# SDRAM.net
KiCad netlist of a schematic drawn in Altium Designer
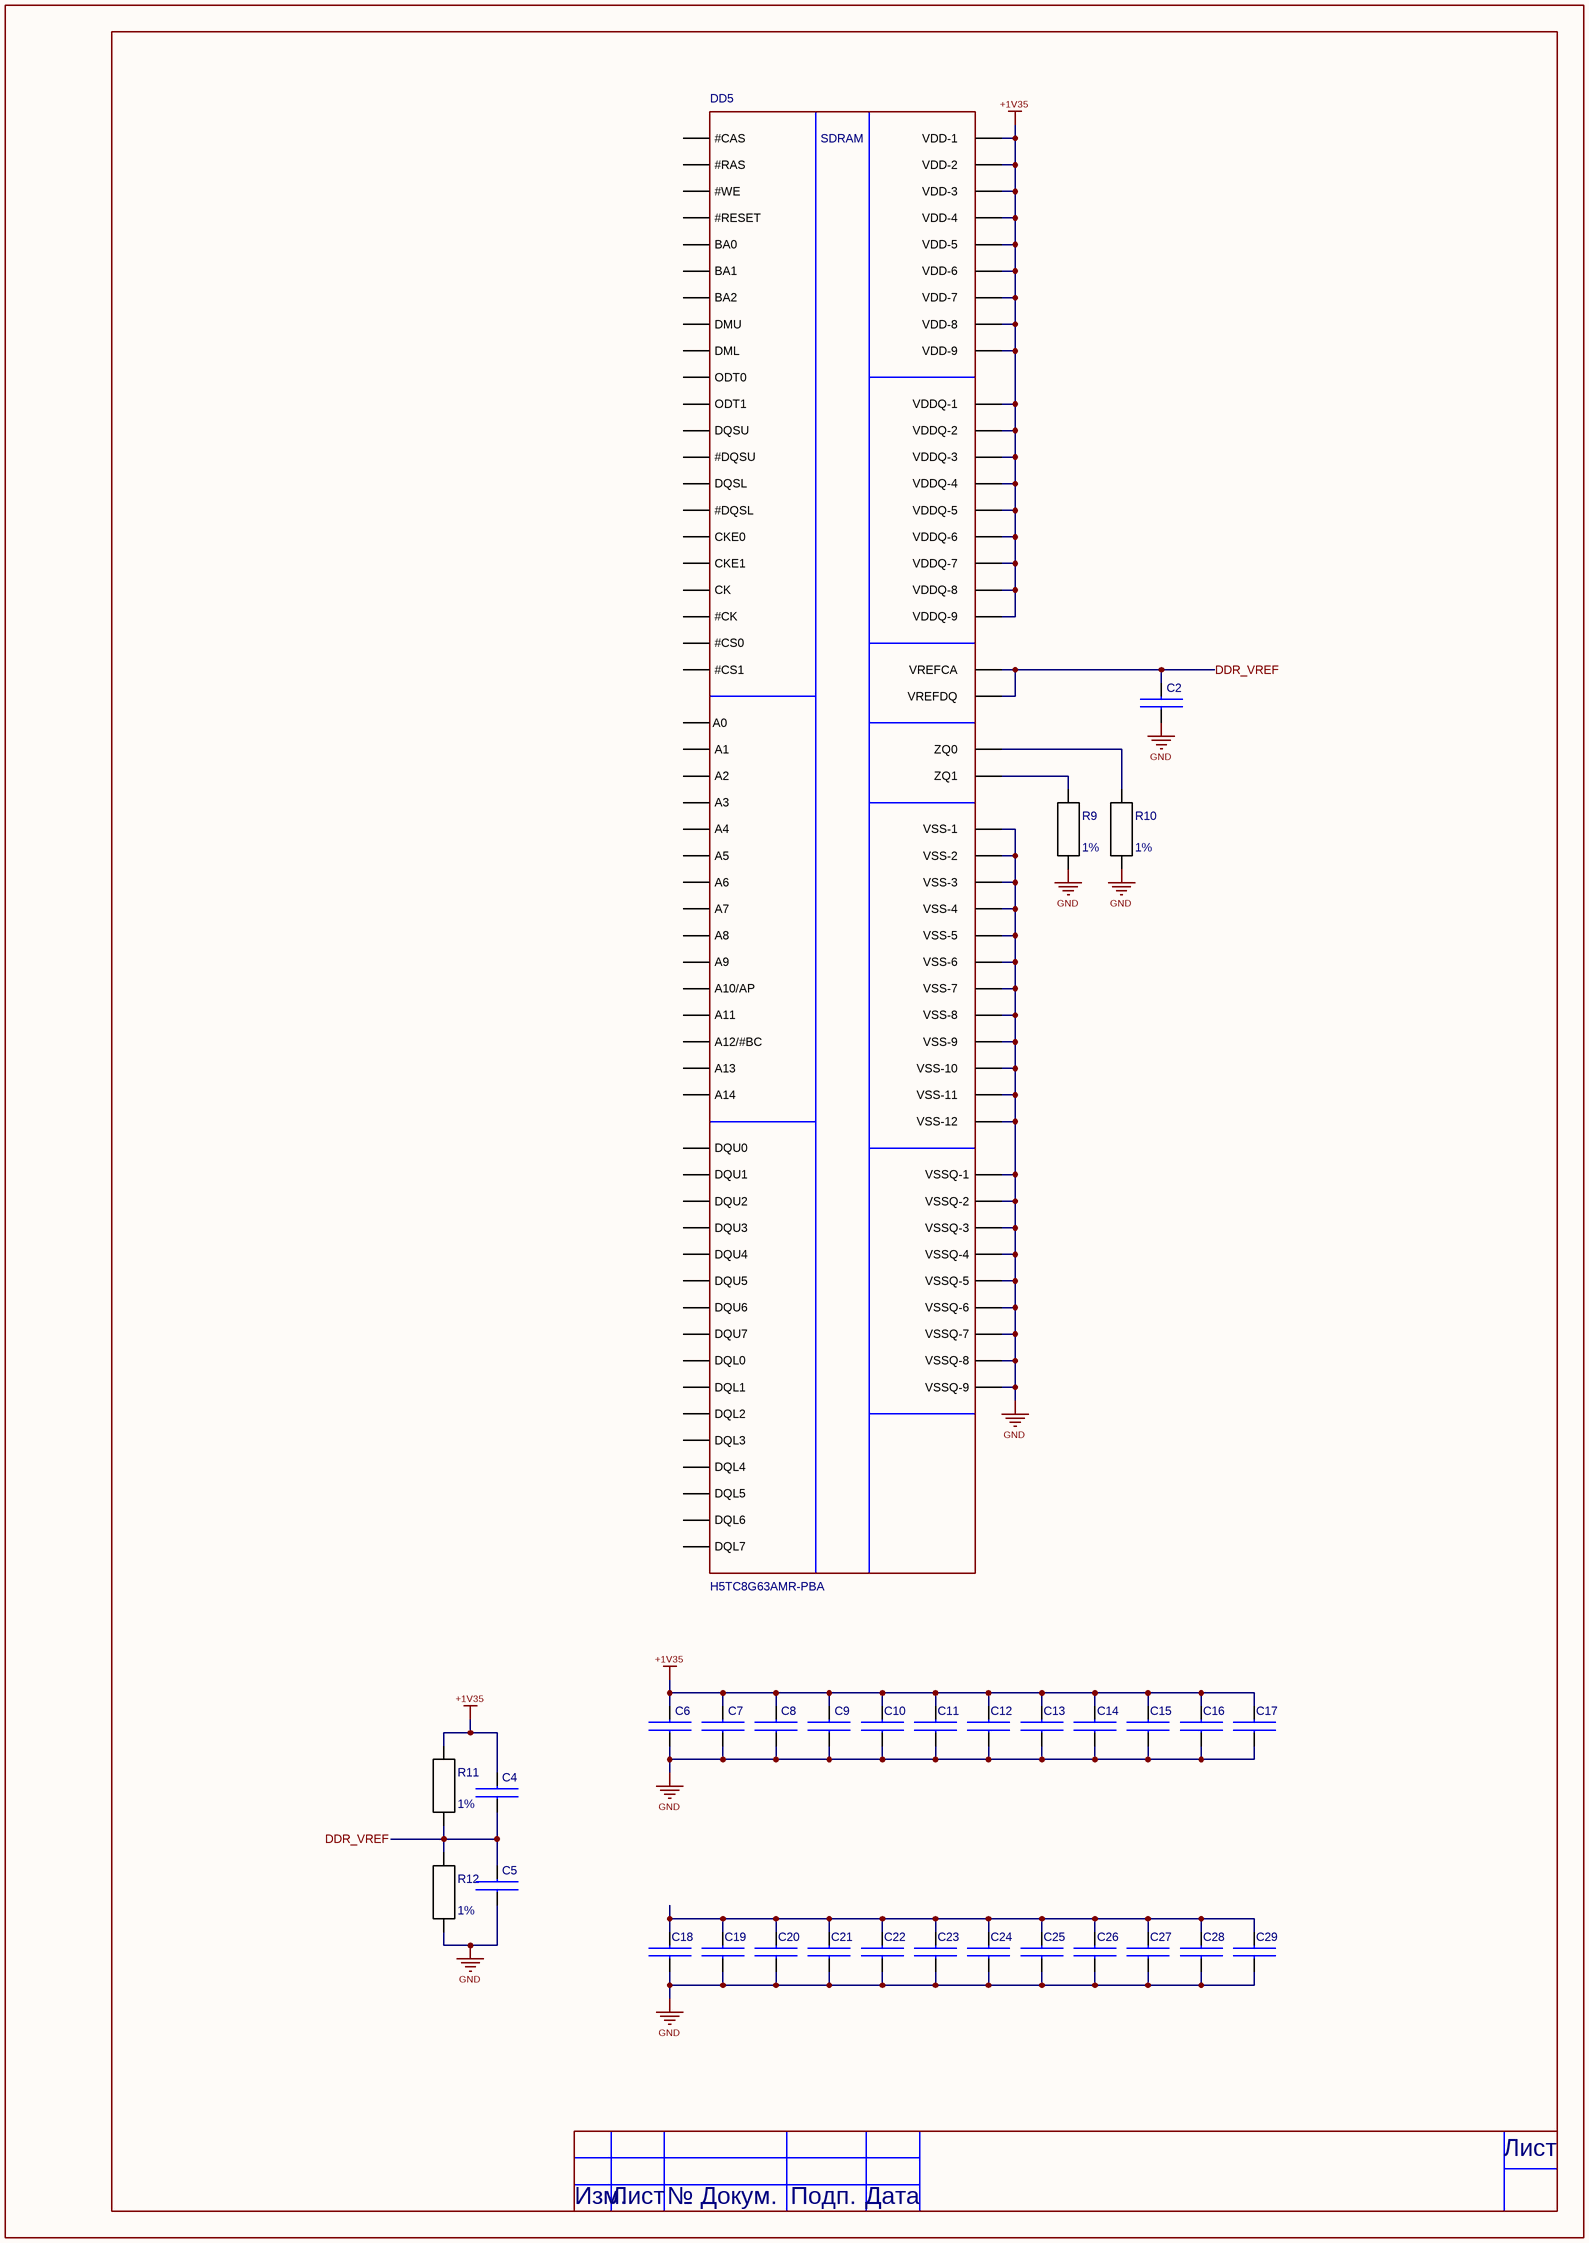
[diagram p0: SDRAM.SchDoc]

(export (version "E")
  (design (tool "Eeschema 10.0.6"))
  (components
    (comp (ref "C2")
      (value "0402-0.1uF-50V-10%-X7R")
      (fields (field (name "TOLERANCE") "10%"))
      (libsource (lib "altium-import") (part "root_1_mirrored__*"))
    )
    (comp (ref "C4")
      (value "0402-0.1uF-50V-10%-X7R")
      (fields (field (name "TOLERANCE") "10%"))
      (libsource (lib "altium-import") (part "root_1__*"))
    )
    (comp (ref "C5")
      (value "0402-0.1uF-50V-10%-X7R")
      (fields (field (name "TOLERANCE") "10%"))
      (libsource (lib "altium-import") (part "root_1__*"))
    )
    (comp (ref "C6")
      (value "0402-0.1uF-50V-10%-X7R")
      (fields (field (name "TOLERANCE") "10%"))
      (libsource (lib "altium-import") (part "root_1__*"))
    )
    (comp (ref "C7")
      (value "0402-0.1uF-50V-10%-X7R")
      (fields (field (name "TOLERANCE") "10%"))
      (libsource (lib "altium-import") (part "root_1__*"))
    )
    (comp (ref "C8")
      (value "0402-0.1uF-50V-10%-X7R")
      (fields (field (name "TOLERANCE") "10%"))
      (libsource (lib "altium-import") (part "root_1__*"))
    )
    (comp (ref "C9")
      (value "0402-0.1uF-50V-10%-X7R")
      (fields (field (name "TOLERANCE") "10%"))
      (libsource (lib "altium-import") (part "root_1__*"))
    )
    (comp (ref "C10")
      (value "0402-0.1uF-50V-10%-X7R")
      (fields (field (name "TOLERANCE") "10%"))
      (libsource (lib "altium-import") (part "root_1__*"))
    )
    (comp (ref "C11")
      (value "0402-0.1uF-50V-10%-X7R")
      (fields (field (name "TOLERANCE") "10%"))
      (libsource (lib "altium-import") (part "root_1__*"))
    )
    (comp (ref "C12")
      (value "0402-0.1uF-50V-10%-X7R")
      (fields (field (name "TOLERANCE") "10%"))
      (libsource (lib "altium-import") (part "root_1__*"))
    )
    (comp (ref "C13")
      (value "0402-0.1uF-50V-10%-X7R")
      (fields (field (name "TOLERANCE") "10%"))
      (libsource (lib "altium-import") (part "root_1__*"))
    )
    (comp (ref "C14")
      (value "0402-0.1uF-50V-10%-X7R")
      (fields (field (name "TOLERANCE") "10%"))
      (libsource (lib "altium-import") (part "root_1__*"))
    )
    (comp (ref "C15")
      (value "0402-0.1uF-50V-10%-X7R")
      (fields (field (name "TOLERANCE") "10%"))
      (libsource (lib "altium-import") (part "root_1__*"))
    )
    (comp (ref "C16")
      (value "0402-0.1uF-50V-10%-X7R")
      (fields (field (name "TOLERANCE") "10%"))
      (libsource (lib "altium-import") (part "root_1__*"))
    )
    (comp (ref "C17")
      (value "0402-0.1uF-50V-10%-X7R")
      (fields (field (name "TOLERANCE") "10%"))
      (libsource (lib "altium-import") (part "root_1__*"))
    )
    (comp (ref "C18")
      (value "0402-0.1uF-50V-10%-X7R")
      (fields (field (name "TOLERANCE") "10%"))
      (libsource (lib "altium-import") (part "root_1__*"))
    )
    (comp (ref "C19")
      (value "0402-0.1uF-50V-10%-X7R")
      (fields (field (name "TOLERANCE") "10%"))
      (libsource (lib "altium-import") (part "root_1__*"))
    )
    (comp (ref "C20")
      (value "0402-0.1uF-50V-10%-X7R")
      (fields (field (name "TOLERANCE") "10%"))
      (libsource (lib "altium-import") (part "root_1__*"))
    )
    (comp (ref "C21")
      (value "0402-0.1uF-50V-10%-X7R")
      (fields (field (name "TOLERANCE") "10%"))
      (libsource (lib "altium-import") (part "root_1__*"))
    )
    (comp (ref "C22")
      (value "0402-0.1uF-50V-10%-X7R")
      (fields (field (name "TOLERANCE") "10%"))
      (libsource (lib "altium-import") (part "root_1__*"))
    )
    (comp (ref "C23")
      (value "0402-0.1uF-50V-10%-X7R")
      (fields (field (name "TOLERANCE") "10%"))
      (libsource (lib "altium-import") (part "root_1__*"))
    )
    (comp (ref "C24")
      (value "0402-0.1uF-50V-10%-X7R")
      (fields (field (name "TOLERANCE") "10%"))
      (libsource (lib "altium-import") (part "root_1__*"))
    )
    (comp (ref "C25")
      (value "0402-0.1uF-50V-10%-X7R")
      (fields (field (name "TOLERANCE") "10%"))
      (libsource (lib "altium-import") (part "root_1__*"))
    )
    (comp (ref "C26")
      (value "0402-0.1uF-50V-10%-X7R")
      (fields (field (name "TOLERANCE") "10%"))
      (libsource (lib "altium-import") (part "root_1__*"))
    )
    (comp (ref "C27")
      (value "0402-0.1uF-50V-10%-X7R")
      (fields (field (name "TOLERANCE") "10%"))
      (libsource (lib "altium-import") (part "root_1__*"))
    )
    (comp (ref "C28")
      (value "0402-0.1uF-50V-10%-X7R")
      (fields (field (name "TOLERANCE") "10%"))
      (libsource (lib "altium-import") (part "root_1__*"))
    )
    (comp (ref "C29")
      (value "0402-0.1uF-50V-10%-X7R")
      (fields (field (name "TOLERANCE") "10%"))
      (libsource (lib "altium-import") (part "root_1__*"))
    )
    (comp (ref "DD5") (value "H5TC8G63AMR-PBA") (libsource (lib "altium-import") (part "root_0__*")))
    (comp (ref "R9")
      (value "0402-243R-1%-1/16 W-100ppm")
      (fields (field (name "TOLERANCE") "1%"))
      (libsource (lib "altium-import") (part "root_3_mirrored__*"))
    )
    (comp (ref "R10")
      (value "0402-243R-1%-1/16 W-100ppm")
      (fields (field (name "TOLERANCE") "1%"))
      (libsource (lib "altium-import") (part "root_3__*"))
    )
    (comp (ref "R11")
      (value "0402-2k-1%-1/16 W-100ppm")
      (fields (field (name "TOLERANCE") "1%"))
      (libsource (lib "") (part "root_1__*_1"))
    )
    (comp (ref "R12")
      (value "0402-2k-1%-1/16 W-100ppm")
      (fields (field (name "TOLERANCE") "1%"))
      (libsource (lib "") (part "root_1__*_1"))
    )
  )
  (nets
    (net (code "1") (name "+1V35") (class "Default")
      (node (ref "C10") (pin "2") (pinfunction "2_2") (pintype "passive"))
      (node (ref "C11") (pin "2") (pinfunction "2_2") (pintype "passive"))
      (node (ref "C12") (pin "2") (pinfunction "2_2") (pintype "passive"))
      (node (ref "C13") (pin "2") (pinfunction "2_2") (pintype "passive"))
      (node (ref "C14") (pin "2") (pinfunction "2_2") (pintype "passive"))
      (node (ref "C15") (pin "2") (pinfunction "2_2") (pintype "passive"))
      (node (ref "C16") (pin "2") (pinfunction "2_2") (pintype "passive"))
      (node (ref "C17") (pin "2") (pinfunction "2_2") (pintype "passive"))
      (node (ref "C4") (pin "2") (pinfunction "2_2") (pintype "passive"))
      (node (ref "C6") (pin "2") (pinfunction "2_2") (pintype "passive"))
      (node (ref "C7") (pin "2") (pinfunction "2_2") (pintype "passive"))
      (node (ref "C8") (pin "2") (pinfunction "2_2") (pintype "passive"))
      (node (ref "C9") (pin "2") (pinfunction "2_2") (pintype "passive"))
      (node (ref "DD5") (pin "A1") (pinfunction "VDDQ-1_A1") (pintype "passive"))
      (node (ref "DD5") (pin "A8") (pinfunction "VDDQ-6_A8") (pintype "passive"))
      (node (ref "DD5") (pin "B2") (pinfunction "VDD-3_B2") (pintype "passive"))
      (node (ref "DD5") (pin "C1") (pinfunction "VDDQ-2_C1") (pintype "passive"))
      (node (ref "DD5") (pin "C9") (pinfunction "VDDQ-7_C9") (pintype "passive"))
      (node (ref "DD5") (pin "D2") (pinfunction "VDDQ-4_D2") (pintype "passive"))
      (node (ref "DD5") (pin "D9") (pinfunction "VDD-7_D9") (pintype "passive"))
      (node (ref "DD5") (pin "E9") (pinfunction "VDDQ-8_E9") (pintype "passive"))
      (node (ref "DD5") (pin "F1") (pinfunction "VDDQ-3_F1") (pintype "passive"))
      (node (ref "DD5") (pin "G7") (pinfunction "VDD-5_G7") (pintype "passive"))
      (node (ref "DD5") (pin "H2") (pinfunction "VDDQ-5_H2") (pintype "passive"))
      (node (ref "DD5") (pin "H9") (pinfunction "VDDQ-9_H9") (pintype "passive"))
      (node (ref "DD5") (pin "K2") (pinfunction "VDD-4_K2") (pintype "passive"))
      (node (ref "DD5") (pin "K8") (pinfunction "VDD-6_K8") (pintype "passive"))
      (node (ref "DD5") (pin "N1") (pinfunction "VDD-1_N1") (pintype "passive"))
      (node (ref "DD5") (pin "N9") (pinfunction "VDD-8_N9") (pintype "passive"))
      (node (ref "DD5") (pin "R1") (pinfunction "VDD-2_R1") (pintype "passive"))
      (node (ref "DD5") (pin "R9") (pinfunction "VDD-9_R9") (pintype "passive"))
      (node (ref "R11") (pin "2") (pinfunction "2_2") (pintype "passive"))
    )
    (net (code "2") (name "/DDR_VREF") (class "Default")
      (node (ref "C2") (pin "2") (pinfunction "2_2") (pintype "passive"))
      (node (ref "C4") (pin "1") (pinfunction "1_1") (pintype "passive"))
      (node (ref "C5") (pin "2") (pinfunction "2_2") (pintype "passive"))
      (node (ref "DD5") (pin "H1") (pinfunction "VREFDQ_H1") (pintype "passive"))
      (node (ref "DD5") (pin "M8") (pinfunction "VREFCA_M8") (pintype "passive"))
      (node (ref "R11") (pin "1") (pinfunction "1_1") (pintype "passive"))
      (node (ref "R12") (pin "2") (pinfunction "2_2") (pintype "passive"))
    )
    (net (code "3") (name "GND") (class "Default")
      (node (ref "C10") (pin "1") (pinfunction "1_1") (pintype "passive"))
      (node (ref "C11") (pin "1") (pinfunction "1_1") (pintype "passive"))
      (node (ref "C12") (pin "1") (pinfunction "1_1") (pintype "passive"))
      (node (ref "C13") (pin "1") (pinfunction "1_1") (pintype "passive"))
      (node (ref "C14") (pin "1") (pinfunction "1_1") (pintype "passive"))
      (node (ref "C15") (pin "1") (pinfunction "1_1") (pintype "passive"))
      (node (ref "C16") (pin "1") (pinfunction "1_1") (pintype "passive"))
      (node (ref "C17") (pin "1") (pinfunction "1_1") (pintype "passive"))
      (node (ref "C18") (pin "1") (pinfunction "1_1") (pintype "passive"))
      (node (ref "C19") (pin "1") (pinfunction "1_1") (pintype "passive"))
      (node (ref "C2") (pin "1") (pinfunction "1_1") (pintype "passive"))
      (node (ref "C20") (pin "1") (pinfunction "1_1") (pintype "passive"))
      (node (ref "C21") (pin "1") (pinfunction "1_1") (pintype "passive"))
      (node (ref "C22") (pin "1") (pinfunction "1_1") (pintype "passive"))
      (node (ref "C23") (pin "1") (pinfunction "1_1") (pintype "passive"))
      (node (ref "C24") (pin "1") (pinfunction "1_1") (pintype "passive"))
      (node (ref "C25") (pin "1") (pinfunction "1_1") (pintype "passive"))
      (node (ref "C26") (pin "1") (pinfunction "1_1") (pintype "passive"))
      (node (ref "C27") (pin "1") (pinfunction "1_1") (pintype "passive"))
      (node (ref "C28") (pin "1") (pinfunction "1_1") (pintype "passive"))
      (node (ref "C29") (pin "1") (pinfunction "1_1") (pintype "passive"))
      (node (ref "C5") (pin "1") (pinfunction "1_1") (pintype "passive"))
      (node (ref "C6") (pin "1") (pinfunction "1_1") (pintype "passive"))
      (node (ref "C7") (pin "1") (pinfunction "1_1") (pintype "passive"))
      (node (ref "C8") (pin "1") (pinfunction "1_1") (pintype "passive"))
      (node (ref "C9") (pin "1") (pinfunction "1_1") (pintype "passive"))
      (node (ref "DD5") (pin "A9") (pinfunction "VSS-9_A9") (pintype "power_in"))
      (node (ref "DD5") (pin "B1") (pinfunction "VSSQ-1_B1") (pintype "power_in"))
      (node (ref "DD5") (pin "B3") (pinfunction "VSS-6_B3") (pintype "power_in"))
      (node (ref "DD5") (pin "B9") (pinfunction "VSSQ-7_B9") (pintype "power_in"))
      (node (ref "DD5") (pin "D1") (pinfunction "VSSQ-2_D1") (pintype "power_in"))
      (node (ref "DD5") (pin "D8") (pinfunction "VSSQ-5_D8") (pintype "power_in"))
      (node (ref "DD5") (pin "E1") (pinfunction "VSS-1_E1") (pintype "power_in"))
      (node (ref "DD5") (pin "E2") (pinfunction "VSSQ-4_E2") (pintype "power_in"))
      (node (ref "DD5") (pin "E8") (pinfunction "VSSQ-6_E8") (pintype "power_in"))
      (node (ref "DD5") (pin "F9") (pinfunction "VSSQ-8_F9") (pintype "power_in"))
      (node (ref "DD5") (pin "G1") (pinfunction "VSSQ-3_G1") (pintype "power_in"))
      (node (ref "DD5") (pin "G8") (pinfunction "VSS-7_G8") (pintype "power_in"))
      (node (ref "DD5") (pin "G9") (pinfunction "VSSQ-9_G9") (pintype "power_in"))
      (node (ref "DD5") (pin "J2") (pinfunction "VSS-5_J2") (pintype "power_in"))
      (node (ref "DD5") (pin "J8") (pinfunction "VSS-8_J8") (pintype "power_in"))
      (node (ref "DD5") (pin "M1") (pinfunction "VSS-2_M1") (pintype "power_in"))
      (node (ref "DD5") (pin "M9") (pinfunction "VSS-10_M9") (pintype "power_in"))
      (node (ref "DD5") (pin "P1") (pinfunction "VSS-3_P1") (pintype "power_in"))
      (node (ref "DD5") (pin "P9") (pinfunction "VSS-11_P9") (pintype "power_in"))
      (node (ref "DD5") (pin "T1") (pinfunction "VSS-4_T1") (pintype "power_in"))
      (node (ref "DD5") (pin "T9") (pinfunction "VSS-12_T9") (pintype "power_in"))
      (node (ref "R10") (pin "2") (pinfunction "2_2") (pintype "passive"))
      (node (ref "R12") (pin "1") (pinfunction "1_1") (pintype "passive"))
      (node (ref "R9") (pin "2") (pinfunction "2_2") (pintype "passive"))
    )
    (net (code "4") (name "Net-(C18-Pad2)") (class "Default")
      (node (ref "C18") (pin "2") (pinfunction "2_2") (pintype "passive"))
      (node (ref "C19") (pin "2") (pinfunction "2_2") (pintype "passive"))
      (node (ref "C20") (pin "2") (pinfunction "2_2") (pintype "passive"))
      (node (ref "C21") (pin "2") (pinfunction "2_2") (pintype "passive"))
      (node (ref "C22") (pin "2") (pinfunction "2_2") (pintype "passive"))
      (node (ref "C23") (pin "2") (pinfunction "2_2") (pintype "passive"))
      (node (ref "C24") (pin "2") (pinfunction "2_2") (pintype "passive"))
      (node (ref "C25") (pin "2") (pinfunction "2_2") (pintype "passive"))
      (node (ref "C26") (pin "2") (pinfunction "2_2") (pintype "passive"))
      (node (ref "C27") (pin "2") (pinfunction "2_2") (pintype "passive"))
      (node (ref "C28") (pin "2") (pinfunction "2_2") (pintype "passive"))
      (node (ref "C29") (pin "2") (pinfunction "2_2") (pintype "passive"))
    )
    (net (code "5") (name "Net-(DD5-ZQ0)") (class "Default")
      (node (ref "DD5") (pin "L8") (pinfunction "ZQ0_L8") (pintype "passive"))
      (node (ref "R10") (pin "1") (pinfunction "1_1") (pintype "passive"))
    )
    (net (code "6") (name "Net-(DD5-ZQ1)") (class "Default")
      (node (ref "DD5") (pin "L9") (pinfunction "ZQ1_L9") (pintype "passive"))
      (node (ref "R9") (pin "1") (pinfunction "1_1") (pintype "passive"))
    )
    (net (code "7") (name "unconnected-(DD5-#CAS-PadK3)") (class "Default")
      (node (ref "DD5") (pin "K3") (pinfunction "#CAS_K3") (pintype "passive"))
    )
    (net (code "8") (name "unconnected-(DD5-#CK-PadK7)") (class "Default")
      (node (ref "DD5") (pin "K7") (pinfunction "#CK_K7") (pintype "passive"))
    )
    (net (code "9") (name "unconnected-(DD5-#CS0-PadL2)") (class "Default")
      (node (ref "DD5") (pin "L2") (pinfunction "#CS0_L2") (pintype "passive"))
    )
    (net (code "10") (name "unconnected-(DD5-#CS1-PadL1)") (class "Default")
      (node (ref "DD5") (pin "L1") (pinfunction "#CS1_L1") (pintype "passive"))
    )
    (net (code "11") (name "unconnected-(DD5-#DQSL-PadG3)") (class "Default")
      (node (ref "DD5") (pin "G3") (pinfunction "#DQSL_G3") (pintype "passive"))
    )
    (net (code "12") (name "unconnected-(DD5-#DQSU-PadB7)") (class "Default")
      (node (ref "DD5") (pin "B7") (pinfunction "#DQSU_B7") (pintype "passive"))
    )
    (net (code "13") (name "unconnected-(DD5-#RAS-PadJ3)") (class "Default")
      (node (ref "DD5") (pin "J3") (pinfunction "#RAS_J3") (pintype "passive"))
    )
    (net (code "14") (name "unconnected-(DD5-#RESET-PadT2)") (class "Default")
      (node (ref "DD5") (pin "T2") (pinfunction "#RESET_T2") (pintype "passive"))
    )
    (net (code "15") (name "unconnected-(DD5-#WE-PadL3)") (class "Default")
      (node (ref "DD5") (pin "L3") (pinfunction "#WE_L3") (pintype "passive"))
    )
    (net (code "16") (name "unconnected-(DD5-A0-PadN3)") (class "Default")
      (node (ref "DD5") (pin "N3") (pinfunction "A0_N3") (pintype "passive"))
    )
    (net (code "17") (name "unconnected-(DD5-A1-PadP7)") (class "Default")
      (node (ref "DD5") (pin "P7") (pinfunction "A1_P7") (pintype "passive"))
    )
    (net (code "18") (name "unconnected-(DD5-A2-PadP3)") (class "Default")
      (node (ref "DD5") (pin "P3") (pinfunction "A2_P3") (pintype "passive"))
    )
    (net (code "19") (name "unconnected-(DD5-A3-PadN2)") (class "Default")
      (node (ref "DD5") (pin "N2") (pinfunction "A3_N2") (pintype "passive"))
    )
    (net (code "20") (name "unconnected-(DD5-A4-PadP8)") (class "Default")
      (node (ref "DD5") (pin "P8") (pinfunction "A4_P8") (pintype "passive"))
    )
    (net (code "21") (name "unconnected-(DD5-A5-PadP2)") (class "Default")
      (node (ref "DD5") (pin "P2") (pinfunction "A5_P2") (pintype "passive"))
    )
    (net (code "22") (name "unconnected-(DD5-A6-PadR8)") (class "Default")
      (node (ref "DD5") (pin "R8") (pinfunction "A6_R8") (pintype "passive"))
    )
    (net (code "23") (name "unconnected-(DD5-A7-PadR2)") (class "Default")
      (node (ref "DD5") (pin "R2") (pinfunction "A7_R2") (pintype "passive"))
    )
    (net (code "24") (name "unconnected-(DD5-A8-PadT8)") (class "Default")
      (node (ref "DD5") (pin "T8") (pinfunction "A8_T8") (pintype "passive"))
    )
    (net (code "25") (name "unconnected-(DD5-A9-PadR3)") (class "Default")
      (node (ref "DD5") (pin "R3") (pinfunction "A9_R3") (pintype "passive"))
    )
    (net (code "26") (name "unconnected-(DD5-A10{slash}AP-PadL7)") (class "Default")
      (node (ref "DD5") (pin "L7") (pinfunction "A10/AP_L7") (pintype "passive"))
    )
    (net (code "27") (name "unconnected-(DD5-A11-PadR7)") (class "Default")
      (node (ref "DD5") (pin "R7") (pinfunction "A11_R7") (pintype "passive"))
    )
    (net (code "28") (name "unconnected-(DD5-A12{slash}#BC-PadN7)") (class "Default")
      (node (ref "DD5") (pin "N7") (pinfunction "A12/#BC_N7") (pintype "passive"))
    )
    (net (code "29") (name "unconnected-(DD5-A13-PadT3)") (class "Default")
      (node (ref "DD5") (pin "T3") (pinfunction "A13_T3") (pintype "passive"))
    )
    (net (code "30") (name "unconnected-(DD5-A14-PadT7)") (class "Default")
      (node (ref "DD5") (pin "T7") (pinfunction "A14_T7") (pintype "passive"))
    )
    (net (code "31") (name "unconnected-(DD5-BA0-PadM2)") (class "Default")
      (node (ref "DD5") (pin "M2") (pinfunction "BA0_M2") (pintype "passive"))
    )
    (net (code "32") (name "unconnected-(DD5-BA1-PadN8)") (class "Default")
      (node (ref "DD5") (pin "N8") (pinfunction "BA1_N8") (pintype "passive"))
    )
    (net (code "33") (name "unconnected-(DD5-BA2-PadM3)") (class "Default")
      (node (ref "DD5") (pin "M3") (pinfunction "BA2_M3") (pintype "passive"))
    )
    (net (code "34") (name "unconnected-(DD5-CK-PadJ7)") (class "Default")
      (node (ref "DD5") (pin "J7") (pinfunction "CK_J7") (pintype "passive"))
    )
    (net (code "35") (name "unconnected-(DD5-CKE0-PadK9)") (class "Default")
      (node (ref "DD5") (pin "K9") (pinfunction "CKE0_K9") (pintype "passive"))
    )
    (net (code "36") (name "unconnected-(DD5-CKE1-PadJ9)") (class "Default")
      (node (ref "DD5") (pin "J9") (pinfunction "CKE1_J9") (pintype "passive"))
    )
    (net (code "37") (name "unconnected-(DD5-DML-PadE7)") (class "Default")
      (node (ref "DD5") (pin "E7") (pinfunction "DML_E7") (pintype "passive"))
    )
    (net (code "38") (name "unconnected-(DD5-DMU-PadD3)") (class "Default")
      (node (ref "DD5") (pin "D3") (pinfunction "DMU_D3") (pintype "passive"))
    )
    (net (code "39") (name "unconnected-(DD5-DQL0-PadE3)") (class "Default")
      (node (ref "DD5") (pin "E3") (pinfunction "DQL0_E3") (pintype "passive"))
    )
    (net (code "40") (name "unconnected-(DD5-DQL1-PadF7)") (class "Default")
      (node (ref "DD5") (pin "F7") (pinfunction "DQL1_F7") (pintype "passive"))
    )
    (net (code "41") (name "unconnected-(DD5-DQL2-PadF2)") (class "Default")
      (node (ref "DD5") (pin "F2") (pinfunction "DQL2_F2") (pintype "passive"))
    )
    (net (code "42") (name "unconnected-(DD5-DQL3-PadF8)") (class "Default")
      (node (ref "DD5") (pin "F8") (pinfunction "DQL3_F8") (pintype "passive"))
    )
    (net (code "43") (name "unconnected-(DD5-DQL4-PadH3)") (class "Default")
      (node (ref "DD5") (pin "H3") (pinfunction "DQL4_H3") (pintype "passive"))
    )
    (net (code "44") (name "unconnected-(DD5-DQL5-PadH8)") (class "Default")
      (node (ref "DD5") (pin "H8") (pinfunction "DQL5_H8") (pintype "passive"))
    )
    (net (code "45") (name "unconnected-(DD5-DQL6-PadG2)") (class "Default")
      (node (ref "DD5") (pin "G2") (pinfunction "DQL6_G2") (pintype "passive"))
    )
    (net (code "46") (name "unconnected-(DD5-DQL7-PadH7)") (class "Default")
      (node (ref "DD5") (pin "H7") (pinfunction "DQL7_H7") (pintype "passive"))
    )
    (net (code "47") (name "unconnected-(DD5-DQSL-PadF3)") (class "Default")
      (node (ref "DD5") (pin "F3") (pinfunction "DQSL_F3") (pintype "passive"))
    )
    (net (code "48") (name "unconnected-(DD5-DQSU-PadC7)") (class "Default")
      (node (ref "DD5") (pin "C7") (pinfunction "DQSU_C7") (pintype "passive"))
    )
    (net (code "49") (name "unconnected-(DD5-DQU0-PadD7)") (class "Default")
      (node (ref "DD5") (pin "D7") (pinfunction "DQU0_D7") (pintype "passive"))
    )
    (net (code "50") (name "unconnected-(DD5-DQU1-PadC3)") (class "Default")
      (node (ref "DD5") (pin "C3") (pinfunction "DQU1_C3") (pintype "passive"))
    )
    (net (code "51") (name "unconnected-(DD5-DQU2-PadC8)") (class "Default")
      (node (ref "DD5") (pin "C8") (pinfunction "DQU2_C8") (pintype "passive"))
    )
    (net (code "52") (name "unconnected-(DD5-DQU3-PadC2)") (class "Default")
      (node (ref "DD5") (pin "C2") (pinfunction "DQU3_C2") (pintype "passive"))
    )
    (net (code "53") (name "unconnected-(DD5-DQU4-PadA7)") (class "Default")
      (node (ref "DD5") (pin "A7") (pinfunction "DQU4_A7") (pintype "passive"))
    )
    (net (code "54") (name "unconnected-(DD5-DQU5-PadA2)") (class "Default")
      (node (ref "DD5") (pin "A2") (pinfunction "DQU5_A2") (pintype "passive"))
    )
    (net (code "55") (name "unconnected-(DD5-DQU6-PadB8)") (class "Default")
      (node (ref "DD5") (pin "B8") (pinfunction "DQU6_B8") (pintype "passive"))
    )
    (net (code "56") (name "unconnected-(DD5-DQU7-PadA3)") (class "Default")
      (node (ref "DD5") (pin "A3") (pinfunction "DQU7_A3") (pintype "passive"))
    )
    (net (code "57") (name "unconnected-(DD5-ODT0-PadK1)") (class "Default")
      (node (ref "DD5") (pin "K1") (pinfunction "ODT0_K1") (pintype "passive"))
    )
    (net (code "58") (name "unconnected-(DD5-ODT1-PadJ1)") (class "Default")
      (node (ref "DD5") (pin "J1") (pinfunction "ODT1_J1") (pintype "passive"))
    )
  )
)
